# airflow_sensor_hot_wire.net
KiCad netlist of a schematic drawn in EAGLE
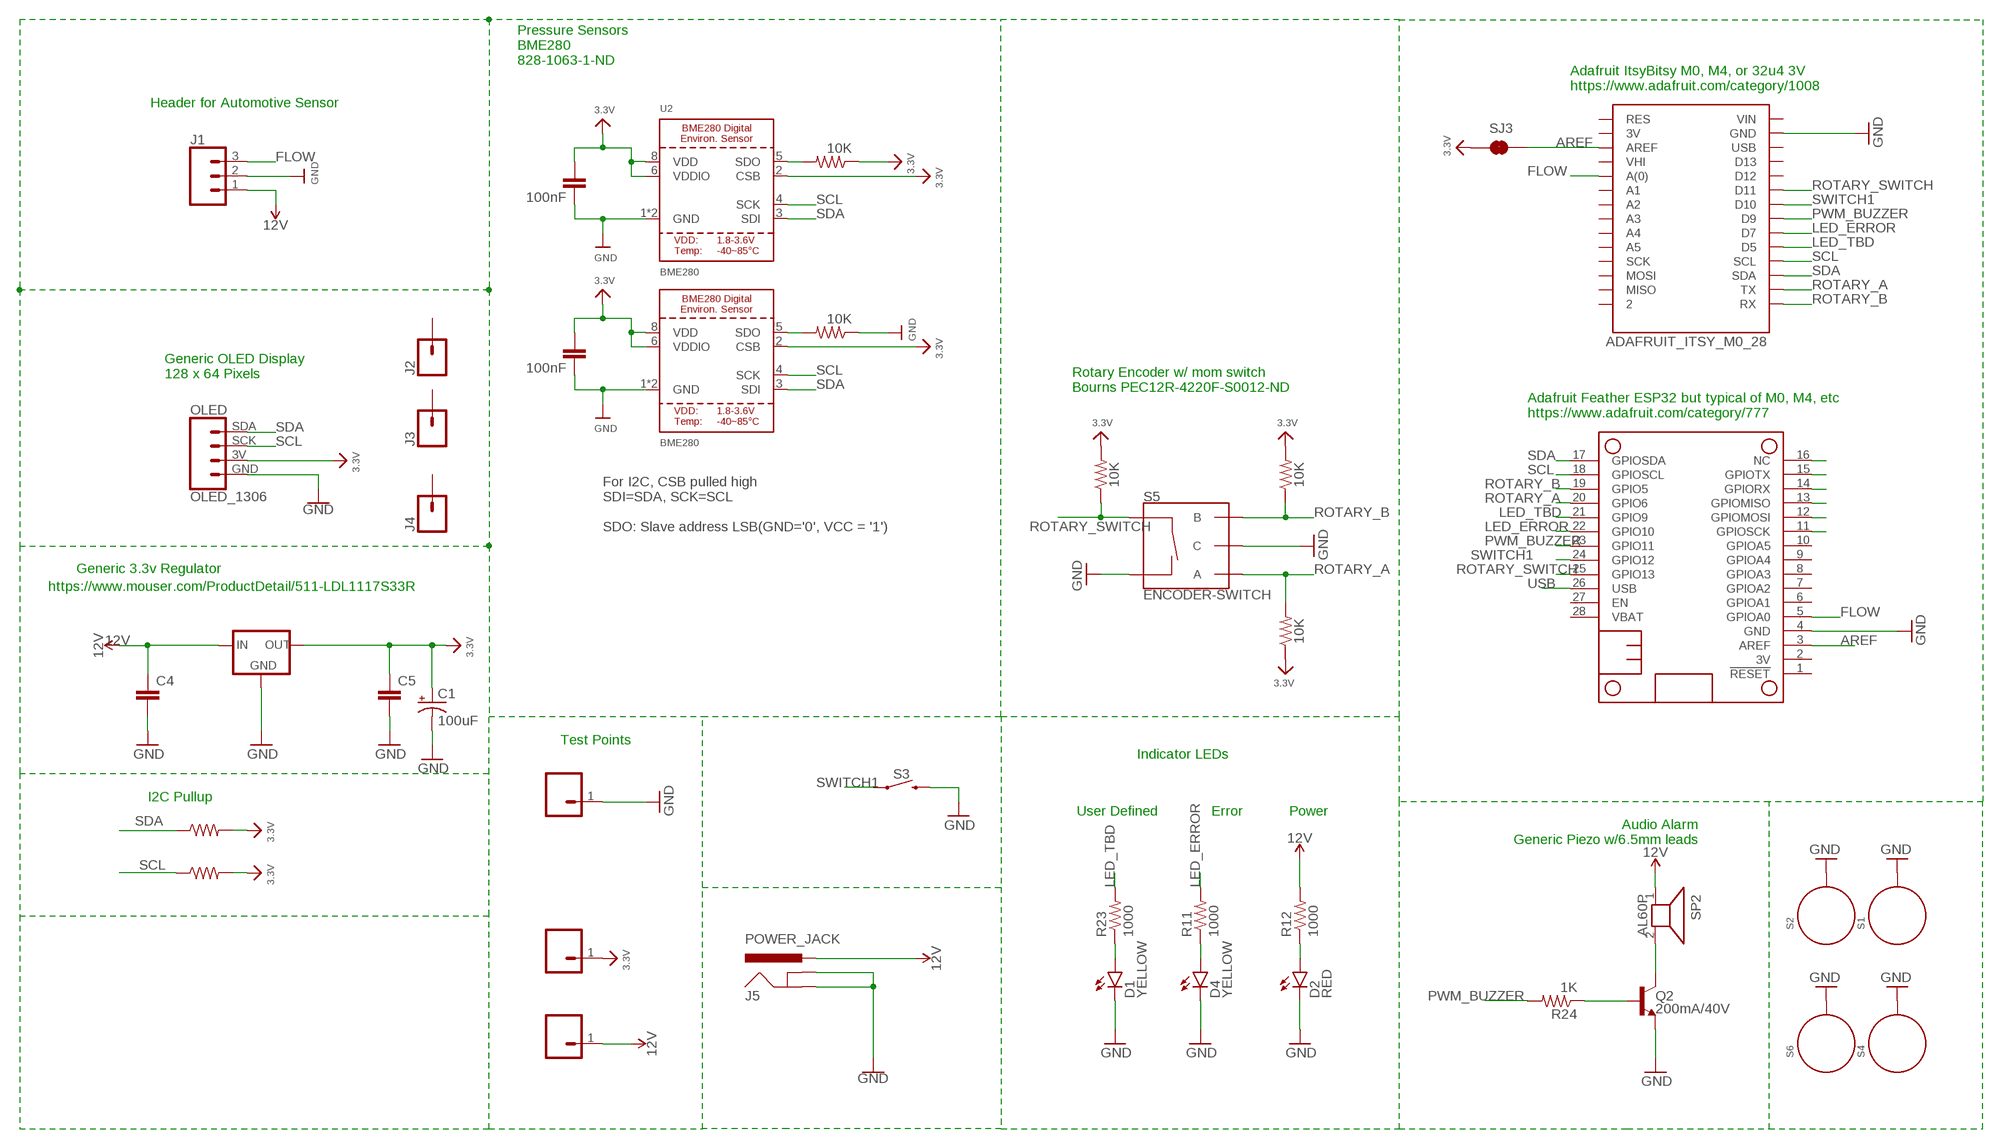
[diagram p0: schematic, sheet 1]

(export (version "E")
  (design (tool "Eeschema 10.0.6"))
  (components
    (comp (ref "3V_REGULATOR")
      (value "LDL1117_5V_REG")
      (footprint "eagle-import:SOT223")
      (libsource (lib "eagle-import") (part "LDL1117_5V_REG"))
    )
    (comp (ref "C1")
      (value "100uF")
      (footprint "eagle-import:CPOL-RADIAL-2.5MM-6.5MM")
      (libsource (lib "eagle-import") (part "100UF-POLAR-RADIAL-2.5MM-25V-20%"))
    )
    (comp (ref "C4")
      (value "CAP-0805")
      (footprint "eagle-import:0805")
      (libsource (lib "eagle-import") (part "CAP-0805"))
    )
    (comp (ref "C5")
      (value "CAP-0805")
      (footprint "eagle-import:0805")
      (libsource (lib "eagle-import") (part "CAP-0805"))
    )
    (comp (ref "C10")
      (value "100nF")
      (footprint "eagle-import:0805")
      (libsource (lib "eagle-import") (part "CAP-0805"))
    )
    (comp (ref "C12")
      (value "100nF")
      (footprint "eagle-import:0805")
      (libsource (lib "eagle-import") (part "CAP-0805"))
    )
    (comp (ref "D1")
      (value "YELLOW")
      (footprint "eagle-import:LED-1206")
      (libsource (lib "eagle-import") (part "LED-YELLOWLARGE"))
    )
    (comp (ref "D2")
      (value "RED")
      (footprint "eagle-import:LED-1206")
      (libsource (lib "eagle-import") (part "LED-RED1206"))
    )
    (comp (ref "D4")
      (value "YELLOW")
      (footprint "eagle-import:LED-1206")
      (libsource (lib "eagle-import") (part "LED-YELLOWLARGE"))
    )
    (comp (ref "J1")
      (value "CONN_03-SCREW-5MM")
      (footprint "eagle-import:SCREWTERMINAL-5MM-3")
      (libsource (lib "eagle-import") (part "CONN_03-SCREW-5MM"))
    )
    (comp (ref "J2")
      (value "CONN_01")
      (footprint "eagle-import:1X01")
      (libsource (lib "eagle-import") (part "CONN_01"))
    )
    (comp (ref "J3")
      (value "CONN_01")
      (footprint "eagle-import:1X01")
      (libsource (lib "eagle-import") (part "CONN_01"))
    )
    (comp (ref "J4")
      (value "CONN_01")
      (footprint "eagle-import:1X01")
      (libsource (lib "eagle-import") (part "CONN_01"))
    )
    (comp (ref "J5")
      (value "POWER_JACK")
      (footprint "eagle-import:POWER_JACK_PTH")
      (libsource (lib "eagle-import") (part "POWER_JACK"))
    )
    (comp (ref "MS2")
      (value "FEATHERWING_NODIM")
      (footprint "eagle-import:FEATHERWING_DIM")
      (libsource (lib "eagle-import") (part "FEATHERWING_NODIM"))
    )
    (comp (ref "Q2")
      (value "200mA/40V")
      (footprint "eagle-import:TO-92")
      (libsource (lib "eagle-import") (part "TRANS_NPN-2N3904"))
    )
    (comp (ref "R1")
      (value "10K")
      (footprint "eagle-import:0805")
      (libsource (lib "eagle-import") (part "RESISTOR0805-RES"))
    )
    (comp (ref "R2")
      (value "10K")
      (footprint "eagle-import:0805")
      (libsource (lib "eagle-import") (part "RESISTOR0805-RES"))
    )
    (comp (ref "R11")
      (value "1000")
      (footprint "eagle-import:0805")
      (libsource (lib "eagle-import") (part "RESISTOR0805-RES"))
    )
    (comp (ref "R12")
      (value "1000")
      (footprint "eagle-import:0805")
      (libsource (lib "eagle-import") (part "RESISTOR0805-RES"))
    )
    (comp (ref "R21")
      (value "0.3")
      (footprint "eagle-import:0805")
      (libsource (lib "eagle-import") (part "0.3OHM-0805-1/8W-1%"))
    )
    (comp (ref "R22")
      (value "0.3")
      (footprint "eagle-import:0805")
      (libsource (lib "eagle-import") (part "0.3OHM-0805-1/8W-1%"))
    )
    (comp (ref "R23")
      (value "1000")
      (footprint "eagle-import:0805")
      (libsource (lib "eagle-import") (part "RESISTOR0805-RES"))
    )
    (comp (ref "R24")
      (value "1K")
      (footprint "eagle-import:0805")
      (libsource (lib "eagle-import") (part "RESISTOR0805-RES"))
    )
    (comp (ref "R26")
      (value "10K")
      (footprint "eagle-import:0805")
      (libsource (lib "eagle-import") (part "0.3OHM-0805-1/8W-1%"))
    )
    (comp (ref "R27")
      (value "10K")
      (footprint "eagle-import:0805")
      (libsource (lib "eagle-import") (part "0.3OHM-0805-1/8W-1%"))
    )
    (comp (ref "R28")
      (value "10K")
      (footprint "eagle-import:0805")
      (libsource (lib "eagle-import") (part "0.3OHM-0805-1/8W-1%"))
    )
    (comp (ref "S1")
      (value "STANDOFF_ELECTRICAL5-32")
      (footprint "eagle-import:STANDOFF_ELECTRICAL_5_32")
      (libsource (lib "eagle-import") (part "STANDOFF_ELECTRICAL5-32"))
    )
    (comp (ref "S2")
      (value "STANDOFF_ELECTRICAL5-32")
      (footprint "eagle-import:STANDOFF_ELECTRICAL_5_32")
      (libsource (lib "eagle-import") (part "STANDOFF_ELECTRICAL5-32"))
    )
    (comp (ref "S3")
      (value "MOMENTARY-SWITCH-SPST-PTH-6.0MM-KIT")
      (footprint "eagle-import:TACTILE_SWITCH_PTH_6.0MM_KIT")
      (libsource (lib "eagle-import") (part "MOMENTARY-SWITCH-SPST-PTH-6.0MM-KIT"))
    )
    (comp (ref "S4")
      (value "STANDOFF_ELECTRICAL5-32")
      (footprint "eagle-import:STANDOFF_ELECTRICAL_5_32")
      (libsource (lib "eagle-import") (part "STANDOFF_ELECTRICAL5-32"))
    )
    (comp (ref "S5")
      (value "ENCODER-SWITCH")
      (footprint "eagle-import:ROTARY_ENC_PLAIN")
      (libsource (lib "eagle-import") (part "ENCODER-SWITCH"))
    )
    (comp (ref "S6")
      (value "STANDOFF_ELECTRICAL5-32")
      (footprint "eagle-import:STANDOFF_ELECTRICAL_5_32")
      (libsource (lib "eagle-import") (part "STANDOFF_ELECTRICAL5-32"))
    )
    (comp (ref "SJ3")
      (value "PWR-LED")
      (footprint "eagle-import:PAD-JUMPER-2-NC_BY_TRACE_NO_SILK")
      (libsource (lib "eagle-import") (part "JUMPER-PAD-2-NC_BY_TRACENO_SILK"))
    )
    (comp (ref "SP2")
      (value "AL60P")
      (footprint "eagle-import:AL60P")
      (libsource (lib "eagle-import") (part "AL60P"))
    )
    (comp (ref "U$1")
      (value "OLED_1306")
      (footprint "eagle-import:OLED_1306")
      (libsource (lib "eagle-import") (part "OLED_1306"))
    )
    (comp (ref "U$20")
      (value "CONN_0138MILL")
      (footprint "eagle-import:1X01-40MILL")
      (libsource (lib "eagle-import") (part "CONN_0138MILL"))
    )
    (comp (ref "U$31")
      (value "CONN_0138MILL")
      (footprint "eagle-import:1X01-40MILL")
      (libsource (lib "eagle-import") (part "CONN_0138MILL"))
    )
    (comp (ref "U$40")
      (value "CONN_0138MILL")
      (footprint "eagle-import:1X01-40MILL")
      (libsource (lib "eagle-import") (part "CONN_0138MILL"))
    )
    (comp (ref "U$45")
      (value "ADAFRUIT_ITSY_M0_28")
      (footprint "eagle-import:ADAFRUIT_ITS_MO_28")
      (libsource (lib "eagle-import") (part "ADAFRUIT_ITSY_M0_28"))
    )
    (comp (ref "U2")
      (value "BME280")
      (footprint "eagle-import:BME280")
      (libsource (lib "eagle-import") (part "BME280"))
    )
    (comp (ref "U4")
      (value "BME280")
      (footprint "eagle-import:BME280")
      (libsource (lib "eagle-import") (part "BME280"))
    )
  )
  (nets
    (net (code "1") (name "/3V") (class "Default")
      (node (ref "MS2") (pin "2") (pinfunction "3V_2") (pintype "power_in"))
    )
    (net (code "2") (name "/AREF") (class "Default")
      (node (ref "MS2") (pin "3") (pinfunction "AREF_3") (pintype "passive"))
      (node (ref "SJ3") (pin "1") (pinfunction "1_1") (pintype "passive"))
      (node (ref "U$45") (pin "AREF") (pinfunction "AREF_AREF") (pintype "bidirectional"))
    )
    (net (code "3") (name "/FLOW") (class "Default")
      (node (ref "J1") (pin "3") (pinfunction "3_3") (pintype "passive"))
      (node (ref "MS2") (pin "5") (pinfunction "GPIOA0_5") (pintype "bidirectional"))
      (node (ref "U$45") (pin "A0") (pinfunction "A(0)_A0") (pintype "bidirectional"))
    )
    (net (code "4") (name "/LED_ERROR") (class "Default")
      (node (ref "MS2") (pin "22") (pinfunction "GPIO10_22") (pintype "bidirectional"))
      (node (ref "R11") (pin "2") (pinfunction "2_2") (pintype "passive"))
      (node (ref "U$45") (pin "D7") (pinfunction "D7_D7") (pintype "bidirectional"))
    )
    (net (code "5") (name "/LED_TBD") (class "Default")
      (node (ref "MS2") (pin "21") (pinfunction "GPIO9_21") (pintype "bidirectional"))
      (node (ref "R23") (pin "2") (pinfunction "2_2") (pintype "passive"))
      (node (ref "U$45") (pin "D5") (pinfunction "D5_D5") (pintype "bidirectional"))
    )
    (net (code "6") (name "/PWM_BUZZER") (class "Default")
      (node (ref "MS2") (pin "23") (pinfunction "GPIO11_23") (pintype "bidirectional"))
      (node (ref "R24") (pin "2") (pinfunction "2_2") (pintype "passive"))
      (node (ref "U$45") (pin "D9") (pinfunction "D9_D9") (pintype "bidirectional"))
    )
    (net (code "7") (name "/ROTARY_A") (class "Default")
      (node (ref "MS2") (pin "20") (pinfunction "GPIO6_20") (pintype "bidirectional"))
      (node (ref "R27") (pin "2") (pinfunction "2_2") (pintype "passive"))
      (node (ref "S5") (pin "A") (pinfunction "A_A") (pintype "bidirectional"))
      (node (ref "U$45") (pin "TX") (pinfunction "TX_TX") (pintype "bidirectional"))
    )
    (net (code "8") (name "/ROTARY_B") (class "Default")
      (node (ref "MS2") (pin "19") (pinfunction "GPIO5_19") (pintype "bidirectional"))
      (node (ref "R26") (pin "1") (pinfunction "1_1") (pintype "passive"))
      (node (ref "S5") (pin "B") (pinfunction "B_B") (pintype "bidirectional"))
      (node (ref "U$45") (pin "RX") (pinfunction "RX_RX") (pintype "bidirectional"))
    )
    (net (code "9") (name "/ROTARY_SWITCH") (class "Default")
      (node (ref "MS2") (pin "25") (pinfunction "GPIO13_25") (pintype "bidirectional"))
      (node (ref "R28") (pin "1") (pinfunction "1_1") (pintype "passive"))
      (node (ref "S5") (pin "SW+") (pinfunction "SW+_SW+") (pintype "bidirectional"))
      (node (ref "U$45") (pin "D11") (pinfunction "D11_D11") (pintype "bidirectional"))
    )
    (net (code "10") (name "/SCL") (class "Default")
      (node (ref "MS2") (pin "18") (pinfunction "GPIOSCL_18") (pintype "bidirectional"))
      (node (ref "R22") (pin "1") (pinfunction "1_1") (pintype "passive"))
      (node (ref "U$1") (pin "SCK") (pinfunction "SCK_SCK") (pintype "passive"))
      (node (ref "U$45") (pin "SCL") (pinfunction "SCL_SCL") (pintype "bidirectional"))
      (node (ref "U2") (pin "4") (pinfunction "SCK_4") (pintype "input"))
      (node (ref "U4") (pin "4") (pinfunction "SCK_4") (pintype "input"))
    )
    (net (code "11") (name "/SDA") (class "Default")
      (node (ref "MS2") (pin "17") (pinfunction "GPIOSDA_17") (pintype "bidirectional"))
      (node (ref "R21") (pin "1") (pinfunction "1_1") (pintype "passive"))
      (node (ref "U$1") (pin "SDA") (pinfunction "SDA_SDA") (pintype "passive"))
      (node (ref "U$45") (pin "SDA") (pinfunction "SDA_SDA") (pintype "bidirectional"))
      (node (ref "U2") (pin "3") (pinfunction "SDI_3") (pintype "input"))
      (node (ref "U4") (pin "3") (pinfunction "SDI_3") (pintype "input"))
    )
    (net (code "12") (name "/SWITCH1") (class "Default")
      (node (ref "MS2") (pin "24") (pinfunction "GPIO12_24") (pintype "bidirectional"))
      (node (ref "S3") (pin "1") (pinfunction "1_1") (pintype "passive"))
      (node (ref "U$45") (pin "D10") (pinfunction "D10_D10") (pintype "bidirectional"))
    )
    (net (code "13") (name "/USB") (class "Default")
      (node (ref "MS2") (pin "26") (pinfunction "USB_26") (pintype "power_in"))
    )
    (net (code "14") (name "/VBAT") (class "Default")
      (node (ref "MS2") (pin "28") (pinfunction "VBAT_28") (pintype "power_in"))
    )
    (net (code "15") (name "3.3V") (class "Default")
      (node (ref "3V_REGULATOR") (pin "2") (pinfunction "OUT_2") (pintype "passive"))
      (node (ref "3V_REGULATOR") (pin "4") (pinfunction "OUT_4") (pintype "passive"))
      (node (ref "C1") (pin "1") (pinfunction "+_1") (pintype "passive"))
      (node (ref "C10") (pin "1") (pinfunction "1_1") (pintype "passive"))
      (node (ref "C12") (pin "1") (pinfunction "1_1") (pintype "passive"))
      (node (ref "C5") (pin "1") (pinfunction "1_1") (pintype "passive"))
      (node (ref "R2") (pin "1") (pinfunction "1_1") (pintype "passive"))
      (node (ref "R21") (pin "2") (pinfunction "2_2") (pintype "passive"))
      (node (ref "R22") (pin "2") (pinfunction "2_2") (pintype "passive"))
      (node (ref "R26") (pin "2") (pinfunction "2_2") (pintype "passive"))
      (node (ref "R27") (pin "1") (pinfunction "1_1") (pintype "passive"))
      (node (ref "R28") (pin "2") (pinfunction "2_2") (pintype "passive"))
      (node (ref "SJ3") (pin "2") (pinfunction "2_2") (pintype "passive"))
      (node (ref "U$1") (pin "3V") (pinfunction "VCC_3V") (pintype "power_in"))
      (node (ref "U$20") (pin "1") (pinfunction "1_1") (pintype "passive"))
      (node (ref "U2") (pin "2") (pinfunction "CSB_2") (pintype "input"))
      (node (ref "U2") (pin "6") (pinfunction "VDDIO_6") (pintype "power_in"))
      (node (ref "U2") (pin "8") (pinfunction "VDD_8") (pintype "power_in"))
      (node (ref "U4") (pin "2") (pinfunction "CSB_2") (pintype "input"))
      (node (ref "U4") (pin "6") (pinfunction "VDDIO_6") (pintype "power_in"))
      (node (ref "U4") (pin "8") (pinfunction "VDD_8") (pintype "power_in"))
    )
    (net (code "16") (name "12V") (class "Default")
      (node (ref "3V_REGULATOR") (pin "3") (pinfunction "IN_3") (pintype "input"))
      (node (ref "C4") (pin "1") (pinfunction "1_1") (pintype "passive"))
      (node (ref "J1") (pin "1") (pinfunction "1_1") (pintype "passive"))
      (node (ref "J5") (pin "PWR") (pinfunction "PWR_PWR") (pintype "bidirectional"))
      (node (ref "R12") (pin "2") (pinfunction "2_2") (pintype "passive"))
      (node (ref "SP2") (pin "1") (pinfunction "1_1") (pintype "passive"))
      (node (ref "U$40") (pin "1") (pinfunction "1_1") (pintype "passive"))
    )
    (net (code "17") (name "GND") (class "Default")
      (node (ref "3V_REGULATOR") (pin "1") (pinfunction "GND_1") (pintype "input"))
      (node (ref "C1") (pin "2") (pinfunction "-_2") (pintype "passive"))
      (node (ref "C10") (pin "2") (pinfunction "2_2") (pintype "passive"))
      (node (ref "C12") (pin "2") (pinfunction "2_2") (pintype "passive"))
      (node (ref "C4") (pin "2") (pinfunction "2_2") (pintype "passive"))
      (node (ref "C5") (pin "2") (pinfunction "2_2") (pintype "passive"))
      (node (ref "D1") (pin "C") (pinfunction "C_C") (pintype "passive"))
      (node (ref "D2") (pin "C") (pinfunction "C_C") (pintype "passive"))
      (node (ref "D4") (pin "C") (pinfunction "C_C") (pintype "passive"))
      (node (ref "J1") (pin "2") (pinfunction "2_2") (pintype "passive"))
      (node (ref "J5") (pin "GND") (pinfunction "GND_GND") (pintype "bidirectional"))
      (node (ref "J5") (pin "GNDBREAK") (pinfunction "GNDBREAK_GNDBREAK") (pintype "bidirectional"))
      (node (ref "MS2") (pin "4") (pinfunction "GND_4") (pintype "power_in"))
      (node (ref "Q2") (pin "1") (pinfunction "E_1") (pintype "passive"))
      (node (ref "R1") (pin "1") (pinfunction "1_1") (pintype "passive"))
      (node (ref "S1") (pin "P1") (pinfunction "P$1_P1") (pintype "bidirectional"))
      (node (ref "S2") (pin "P1") (pinfunction "P$1_P1") (pintype "bidirectional"))
      (node (ref "S3") (pin "3") (pinfunction "2_3") (pintype "passive"))
      (node (ref "S4") (pin "P1") (pinfunction "P$1_P1") (pintype "bidirectional"))
      (node (ref "S5") (pin "C") (pinfunction "C_C") (pintype "bidirectional"))
      (node (ref "S5") (pin "SW-") (pinfunction "SW-_SW-") (pintype "bidirectional"))
      (node (ref "S6") (pin "P1") (pinfunction "P$1_P1") (pintype "bidirectional"))
      (node (ref "U$1") (pin "GND") (pinfunction "GND_GND") (pintype "passive"))
      (node (ref "U$31") (pin "1") (pinfunction "1_1") (pintype "passive"))
      (node (ref "U$45") (pin "GND") (pinfunction "GND_GND") (pintype "bidirectional"))
      (node (ref "U2") (pin "1") (pinfunction "GND_1") (pintype "power_in"))
      (node (ref "U2") (pin "7") (pinfunction "GND_7") (pintype "power_in"))
      (node (ref "U4") (pin "1") (pinfunction "GND_1") (pintype "power_in"))
      (node (ref "U4") (pin "7") (pinfunction "GND_7") (pintype "power_in"))
    )
    (net (code "18") (name "Net-(D1-PadA)") (class "Default")
      (node (ref "D1") (pin "A") (pinfunction "A_A") (pintype "passive"))
      (node (ref "R23") (pin "1") (pinfunction "1_1") (pintype "passive"))
    )
    (net (code "19") (name "Net-(D2-PadA)") (class "Default")
      (node (ref "D2") (pin "A") (pinfunction "A_A") (pintype "passive"))
      (node (ref "R12") (pin "1") (pinfunction "1_1") (pintype "passive"))
    )
    (net (code "20") (name "Net-(D4-PadA)") (class "Default")
      (node (ref "D4") (pin "A") (pinfunction "A_A") (pintype "passive"))
      (node (ref "R11") (pin "1") (pinfunction "1_1") (pintype "passive"))
    )
    (net (code "21") (name "Net-(Q2-B)") (class "Default")
      (node (ref "Q2") (pin "2") (pinfunction "B_2") (pintype "passive"))
      (node (ref "R24") (pin "1") (pinfunction "1_1") (pintype "passive"))
    )
    (net (code "22") (name "Net-(Q2-C)") (class "Default")
      (node (ref "Q2") (pin "3") (pinfunction "C_3") (pintype "passive"))
      (node (ref "SP2") (pin "2") (pinfunction "2_2") (pintype "passive"))
    )
    (net (code "23") (name "Net-(U2-SDO)") (class "Default")
      (node (ref "R2") (pin "2") (pinfunction "2_2") (pintype "passive"))
      (node (ref "U2") (pin "5") (pinfunction "SDO_5") (pintype "output"))
    )
    (net (code "24") (name "Net-(U4-SDO)") (class "Default")
      (node (ref "R1") (pin "2") (pinfunction "2_2") (pintype "passive"))
      (node (ref "U4") (pin "5") (pinfunction "SDO_5") (pintype "output"))
    )
    (net (code "25") (name "unconnected-(J2-Pad1)") (class "Default")
      (node (ref "J2") (pin "1") (pinfunction "1_1") (pintype "passive"))
    )
    (net (code "26") (name "unconnected-(J3-Pad1)") (class "Default")
      (node (ref "J3") (pin "1") (pinfunction "1_1") (pintype "passive"))
    )
    (net (code "27") (name "unconnected-(J4-Pad1)") (class "Default")
      (node (ref "J4") (pin "1") (pinfunction "1_1") (pintype "passive"))
    )
    (net (code "28") (name "unconnected-(MS2-EN-Pad27)") (class "Default")
      (node (ref "MS2") (pin "27") (pinfunction "EN_27") (pintype "passive"))
    )
    (net (code "29") (name "unconnected-(MS2-GPIOA1-Pad6)") (class "Default")
      (node (ref "MS2") (pin "6") (pinfunction "GPIOA1_6") (pintype "bidirectional"))
    )
    (net (code "30") (name "unconnected-(MS2-GPIOA2-Pad7)") (class "Default")
      (node (ref "MS2") (pin "7") (pinfunction "GPIOA2_7") (pintype "bidirectional"))
    )
    (net (code "31") (name "unconnected-(MS2-GPIOA3-Pad8)") (class "Default")
      (node (ref "MS2") (pin "8") (pinfunction "GPIOA3_8") (pintype "bidirectional"))
    )
    (net (code "32") (name "unconnected-(MS2-GPIOA4-Pad9)") (class "Default")
      (node (ref "MS2") (pin "9") (pinfunction "GPIOA4_9") (pintype "bidirectional"))
    )
    (net (code "33") (name "unconnected-(MS2-GPIOA5-Pad10)") (class "Default")
      (node (ref "MS2") (pin "10") (pinfunction "GPIOA5_10") (pintype "bidirectional"))
    )
    (net (code "34") (name "unconnected-(MS2-GPIOMISO-Pad13)") (class "Default")
      (node (ref "MS2") (pin "13") (pinfunction "GPIOMISO_13") (pintype "bidirectional"))
    )
    (net (code "35") (name "unconnected-(MS2-GPIOMOSI-Pad12)") (class "Default")
      (node (ref "MS2") (pin "12") (pinfunction "GPIOMOSI_12") (pintype "bidirectional"))
    )
    (net (code "36") (name "unconnected-(MS2-GPIORX-Pad14)") (class "Default")
      (node (ref "MS2") (pin "14") (pinfunction "GPIORX_14") (pintype "bidirectional"))
    )
    (net (code "37") (name "unconnected-(MS2-GPIOSCK-Pad11)") (class "Default")
      (node (ref "MS2") (pin "11") (pinfunction "GPIOSCK_11") (pintype "bidirectional"))
    )
    (net (code "38") (name "unconnected-(MS2-GPIOTX-Pad15)") (class "Default")
      (node (ref "MS2") (pin "15") (pinfunction "GPIOTX_15") (pintype "bidirectional"))
    )
    (net (code "39") (name "unconnected-(MS2-NC-Pad16)") (class "Default")
      (node (ref "MS2") (pin "16") (pinfunction "NC_16") (pintype "passive"))
    )
    (net (code "40") (name "unconnected-(MS2-~{RESET}-Pad1)") (class "Default")
      (node (ref "MS2") (pin "1") (pinfunction "~{RESET}_1") (pintype "input"))
    )
    (net (code "41") (name "unconnected-(U$45-Pad2)") (class "Default")
      (node (ref "U$45") (pin "2") (pinfunction "2_2") (pintype "bidirectional"))
    )
    (net (code "42") (name "unconnected-(U$45-Pad3V)") (class "Default")
      (node (ref "U$45") (pin "3V") (pinfunction "3V_3V") (pintype "bidirectional"))
    )
    (net (code "43") (name "unconnected-(U$45-PadA1)") (class "Default")
      (node (ref "U$45") (pin "A1") (pinfunction "A1_A1") (pintype "bidirectional"))
    )
    (net (code "44") (name "unconnected-(U$45-PadA2)") (class "Default")
      (node (ref "U$45") (pin "A2") (pinfunction "A2_A2") (pintype "bidirectional"))
    )
    (net (code "45") (name "unconnected-(U$45-PadA3)") (class "Default")
      (node (ref "U$45") (pin "A3") (pinfunction "A3_A3") (pintype "bidirectional"))
    )
    (net (code "46") (name "unconnected-(U$45-PadA4)") (class "Default")
      (node (ref "U$45") (pin "A4") (pinfunction "A4_A4") (pintype "bidirectional"))
    )
    (net (code "47") (name "unconnected-(U$45-PadA5)") (class "Default")
      (node (ref "U$45") (pin "A5") (pinfunction "A5_A5") (pintype "bidirectional"))
    )
    (net (code "48") (name "unconnected-(U$45-PadD12)") (class "Default")
      (node (ref "U$45") (pin "D12") (pinfunction "D12_D12") (pintype "bidirectional"))
    )
    (net (code "49") (name "unconnected-(U$45-PadD13)") (class "Default")
      (node (ref "U$45") (pin "D13") (pinfunction "D13_D13") (pintype "bidirectional"))
    )
    (net (code "50") (name "unconnected-(U$45-PadMISO)") (class "Default")
      (node (ref "U$45") (pin "MISO") (pinfunction "MISO_MISO") (pintype "bidirectional"))
    )
    (net (code "51") (name "unconnected-(U$45-PadMOSI)") (class "Default")
      (node (ref "U$45") (pin "MOSI") (pinfunction "MOSI_MOSI") (pintype "bidirectional"))
    )
    (net (code "52") (name "unconnected-(U$45-PadRES)") (class "Default")
      (node (ref "U$45") (pin "RES") (pinfunction "RES_RES") (pintype "bidirectional"))
    )
    (net (code "53") (name "unconnected-(U$45-PadSCK)") (class "Default")
      (node (ref "U$45") (pin "SCK") (pinfunction "SCK_SCK") (pintype "bidirectional"))
    )
    (net (code "54") (name "unconnected-(U$45-PadUSB)") (class "Default")
      (node (ref "U$45") (pin "USB") (pinfunction "USB_USB") (pintype "bidirectional"))
    )
    (net (code "55") (name "unconnected-(U$45-PadVHI)") (class "Default")
      (node (ref "U$45") (pin "VHI") (pinfunction "VHI_VHI") (pintype "bidirectional"))
    )
    (net (code "56") (name "unconnected-(U$45-PadVIN)") (class "Default")
      (node (ref "U$45") (pin "VIN") (pinfunction "VIN_VIN") (pintype "bidirectional"))
    )
  )
)
